# Adafruit_ADG728_1-to-8_Analog_Matrix_Swi.net
KiCad netlist of a schematic drawn in EAGLE
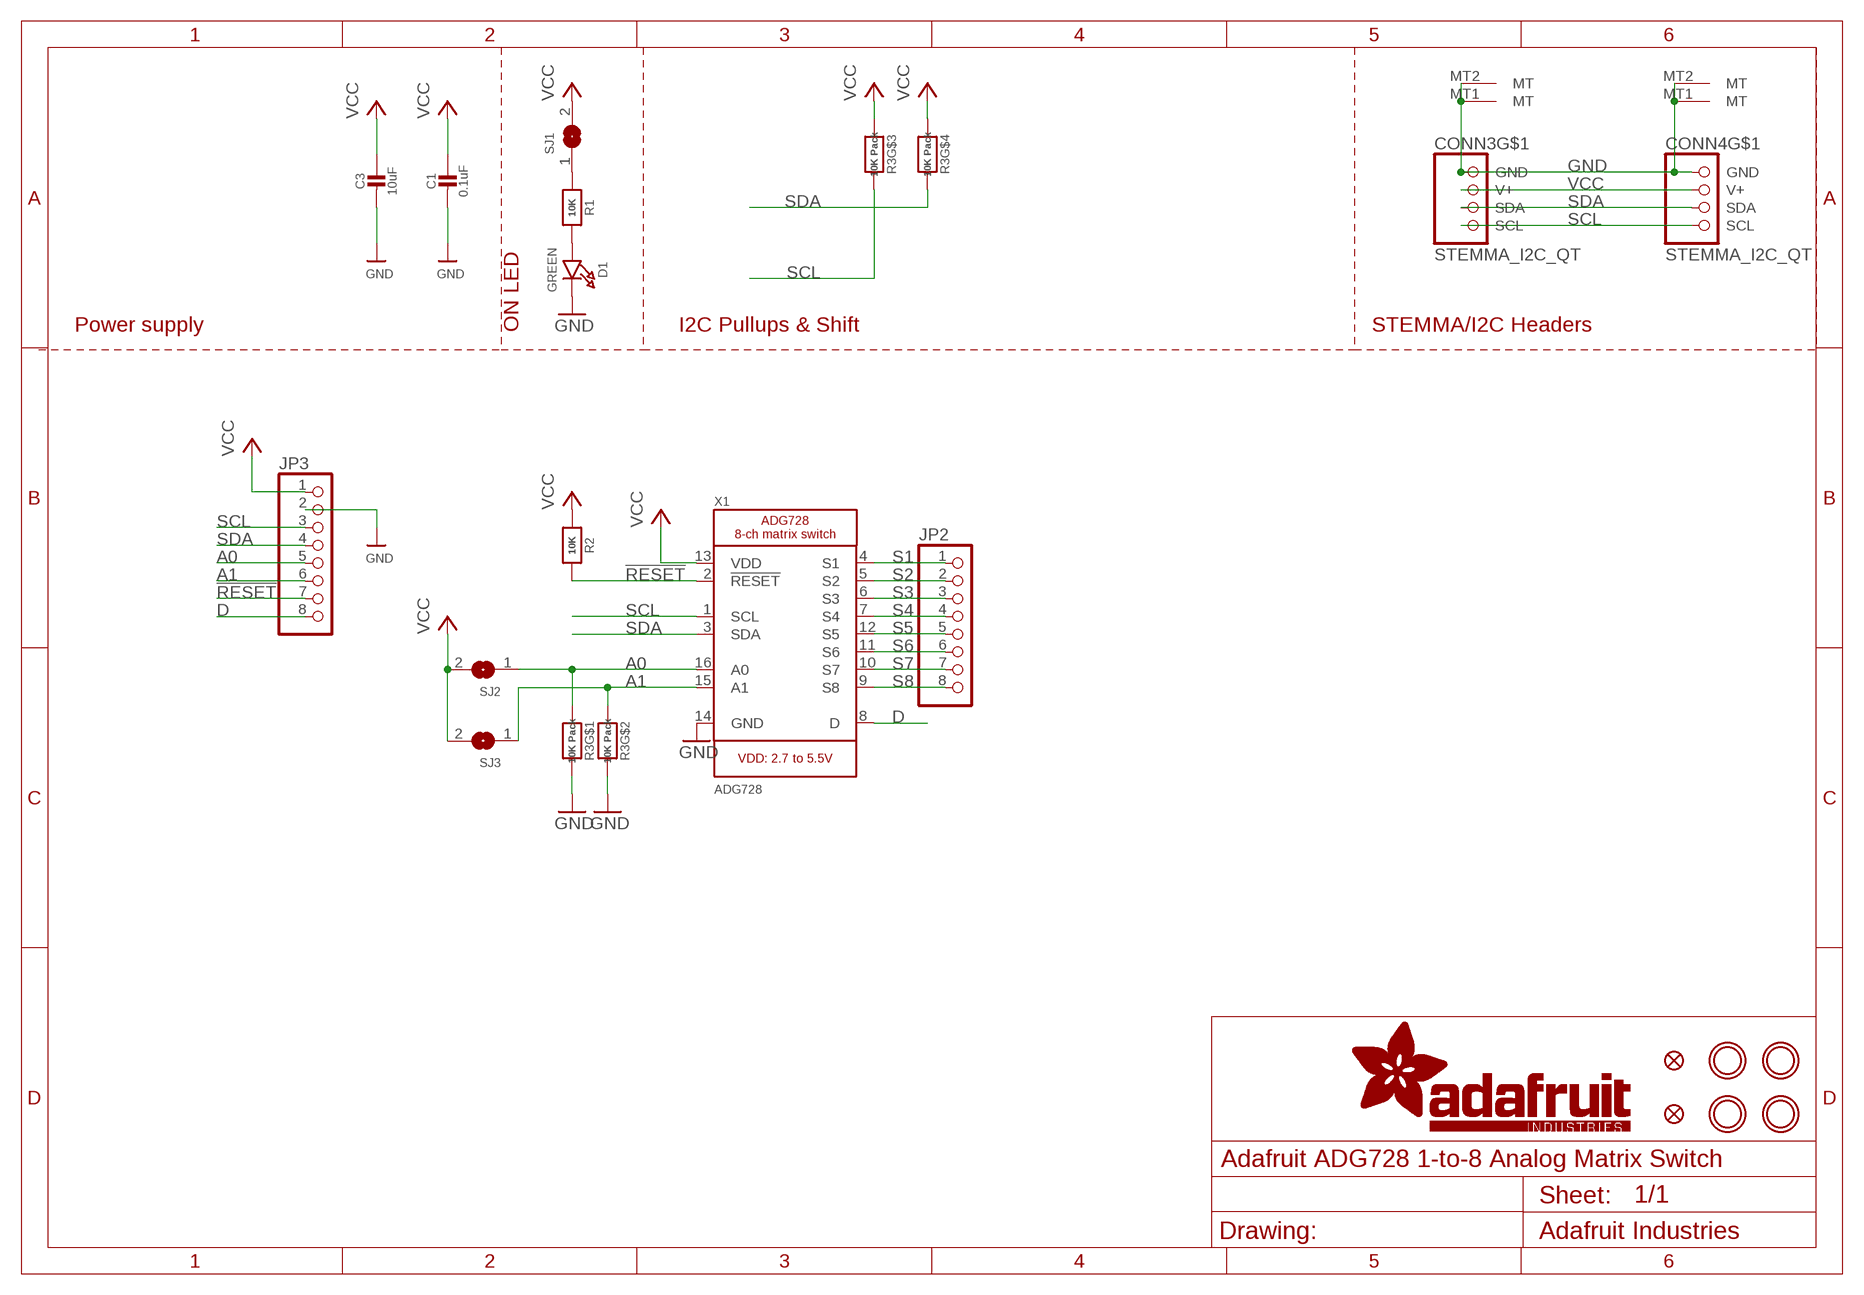
[diagram p0: schematic, sheet 1]

(export (version "E")
  (design (tool "Eeschema 10.0.6"))
  (components
    (comp (ref "C1")
      (value "0.1uF")
      (footprint "eagle-import:0603-NO")
      (libsource (lib "eagle-import") (part "CAP_CERAMIC0603_NO"))
    )
    (comp (ref "C3")
      (value "10uF")
      (footprint "eagle-import:0805-NO")
      (libsource (lib "eagle-import") (part "CAP_CERAMIC0805-NOOUTLINE"))
    )
    (comp (ref "CONN3")
      (value "STEMMA_I2C_QT")
      (footprint "eagle-import:JST_SH4")
      (libsource (lib "eagle-import") (part "STEMMA_I2C_QT"))
    )
    (comp (ref "CONN4")
      (value "STEMMA_I2C_QT")
      (footprint "eagle-import:JST_SH4")
      (libsource (lib "eagle-import") (part "STEMMA_I2C_QT"))
    )
    (comp (ref "D1")
      (value "GREEN")
      (footprint "eagle-import:CHIPLED_0603_NOOUTLINE")
      (libsource (lib "eagle-import") (part "LED0603_NOOUTLINE"))
    )
    (comp (ref "FID3")
      (value "FIDUCIAL_1MM")
      (footprint "eagle-import:FIDUCIAL_1MM")
      (libsource (lib "eagle-import") (part "FIDUCIAL_1MM"))
    )
    (comp (ref "FID4")
      (value "FIDUCIAL_1MM")
      (footprint "eagle-import:FIDUCIAL_1MM")
      (libsource (lib "eagle-import") (part "FIDUCIAL_1MM"))
    )
    (comp (ref "JP2")
      (value "HEADER-1X870MIL")
      (footprint "eagle-import:1X08_ROUND_70")
      (libsource (lib "eagle-import") (part "HEADER-1X870MIL"))
    )
    (comp (ref "JP3")
      (value "HEADER-1X870MIL")
      (footprint "eagle-import:1X08_ROUND_70")
      (libsource (lib "eagle-import") (part "HEADER-1X870MIL"))
    )
    (comp (ref "R1")
      (value "10K")
      (footprint "eagle-import:0603-NO")
      (libsource (lib "eagle-import") (part "RESISTOR_0603_NOOUT"))
    )
    (comp (ref "R2")
      (value "10K")
      (footprint "eagle-import:0603-NO")
      (libsource (lib "eagle-import") (part "RESISTOR_0603_NOOUT"))
    )
    (comp (ref "R3")
      (value "10K Pack")
      (footprint "eagle-import:RESPACK_4X0603")
      (libsource (lib "eagle-import") (part "RESISTOR_4PACK"))
    )
    (comp (ref "SJ1")
      (value "SOLDERJUMPERCLOSED")
      (footprint "eagle-import:SOLDERJUMPER_CLOSEDWIRE")
      (libsource (lib "eagle-import") (part "SOLDERJUMPERCLOSED"))
    )
    (comp (ref "SJ2")
      (value "SOLDERJUMPER")
      (footprint "eagle-import:SOLDERJUMPER_ARROW_NOPASTE")
      (libsource (lib "eagle-import") (part "SOLDERJUMPER"))
    )
    (comp (ref "SJ3")
      (value "SOLDERJUMPER")
      (footprint "eagle-import:SOLDERJUMPER_ARROW_NOPASTE")
      (libsource (lib "eagle-import") (part "SOLDERJUMPER"))
    )
    (comp (ref "U$1")
      (value "MOUNTINGHOLE2.5")
      (footprint "eagle-import:MOUNTINGHOLE_2.5_PLATED")
      (libsource (lib "eagle-import") (part "MOUNTINGHOLE2.5"))
    )
    (comp (ref "U$17")
      (value "MOUNTINGHOLE2.5")
      (footprint "eagle-import:MOUNTINGHOLE_2.5_PLATED")
      (libsource (lib "eagle-import") (part "MOUNTINGHOLE2.5"))
    )
    (comp (ref "U$19")
      (value "MOUNTINGHOLE2.5")
      (footprint "eagle-import:MOUNTINGHOLE_2.5_PLATED")
      (libsource (lib "eagle-import") (part "MOUNTINGHOLE2.5"))
    )
    (comp (ref "U$21")
      (value "MOUNTINGHOLE2.5")
      (footprint "eagle-import:MOUNTINGHOLE_2.5_PLATED")
      (libsource (lib "eagle-import") (part "MOUNTINGHOLE2.5"))
    )
    (comp (ref "X1")
      (value "ADG728")
      (footprint "eagle-import:TSSOP16")
      (libsource (lib "eagle-import") (part "ADG728"))
    )
  )
  (nets
    (net (code "1") (name "/A0") (class "Default")
      (node (ref "JP3") (pin "5") (pinfunction "5_5") (pintype "passive"))
      (node (ref "R3") (pin "1") (pinfunction "1_1") (pintype "passive"))
      (node (ref "SJ2") (pin "1") (pinfunction "1_1") (pintype "passive"))
      (node (ref "X1") (pin "16") (pinfunction "A0_16") (pintype "input"))
    )
    (net (code "2") (name "/A1") (class "Default")
      (node (ref "JP3") (pin "6") (pinfunction "6_6") (pintype "passive"))
      (node (ref "R3") (pin "2") (pinfunction "1_2") (pintype "passive"))
      (node (ref "SJ3") (pin "1") (pinfunction "1_1") (pintype "passive"))
      (node (ref "X1") (pin "15") (pinfunction "A1_15") (pintype "input"))
    )
    (net (code "3") (name "/D") (class "Default")
      (node (ref "JP3") (pin "8") (pinfunction "8_8") (pintype "passive"))
      (node (ref "X1") (pin "8") (pinfunction "D_8") (pintype "input"))
    )
    (net (code "4") (name "/S1") (class "Default")
      (node (ref "JP2") (pin "1") (pinfunction "1_1") (pintype "passive"))
      (node (ref "X1") (pin "4") (pinfunction "S1_4") (pintype "input"))
    )
    (net (code "5") (name "/S2") (class "Default")
      (node (ref "JP2") (pin "2") (pinfunction "2_2") (pintype "passive"))
      (node (ref "X1") (pin "5") (pinfunction "S2_5") (pintype "input"))
    )
    (net (code "6") (name "/S3") (class "Default")
      (node (ref "JP2") (pin "3") (pinfunction "3_3") (pintype "passive"))
      (node (ref "X1") (pin "6") (pinfunction "S3_6") (pintype "input"))
    )
    (net (code "7") (name "/S4") (class "Default")
      (node (ref "JP2") (pin "4") (pinfunction "4_4") (pintype "passive"))
      (node (ref "X1") (pin "7") (pinfunction "S4_7") (pintype "input"))
    )
    (net (code "8") (name "/S5") (class "Default")
      (node (ref "JP2") (pin "5") (pinfunction "5_5") (pintype "passive"))
      (node (ref "X1") (pin "12") (pinfunction "S5_12") (pintype "input"))
    )
    (net (code "9") (name "/S6") (class "Default")
      (node (ref "JP2") (pin "6") (pinfunction "6_6") (pintype "passive"))
      (node (ref "X1") (pin "11") (pinfunction "S6_11") (pintype "input"))
    )
    (net (code "10") (name "/S7") (class "Default")
      (node (ref "JP2") (pin "7") (pinfunction "7_7") (pintype "passive"))
      (node (ref "X1") (pin "10") (pinfunction "S7_10") (pintype "input"))
    )
    (net (code "11") (name "/S8") (class "Default")
      (node (ref "JP2") (pin "8") (pinfunction "8_8") (pintype "passive"))
      (node (ref "X1") (pin "9") (pinfunction "S8_9") (pintype "input"))
    )
    (net (code "12") (name "/SCL") (class "Default")
      (node (ref "CONN3") (pin "4") (pinfunction "SCL_4") (pintype "passive"))
      (node (ref "CONN4") (pin "4") (pinfunction "SCL_4") (pintype "passive"))
      (node (ref "JP3") (pin "3") (pinfunction "3_3") (pintype "passive"))
      (node (ref "R3") (pin "6") (pinfunction "2_6") (pintype "passive"))
      (node (ref "X1") (pin "1") (pinfunction "SCL_1") (pintype "bidirectional"))
    )
    (net (code "13") (name "/SDA") (class "Default")
      (node (ref "CONN3") (pin "3") (pinfunction "SDA_3") (pintype "passive"))
      (node (ref "CONN4") (pin "3") (pinfunction "SDA_3") (pintype "passive"))
      (node (ref "JP3") (pin "4") (pinfunction "4_4") (pintype "passive"))
      (node (ref "R3") (pin "5") (pinfunction "2_5") (pintype "passive"))
      (node (ref "X1") (pin "3") (pinfunction "SDA_3") (pintype "bidirectional"))
    )
    (net (code "14") (name "/~{RESET}") (class "Default")
      (node (ref "JP3") (pin "7") (pinfunction "7_7") (pintype "passive"))
      (node (ref "R2") (pin "2") (pinfunction "2_2") (pintype "passive"))
      (node (ref "X1") (pin "2") (pinfunction "~{RESET}_2") (pintype "input"))
    )
    (net (code "15") (name "GND") (class "Default")
      (node (ref "C1") (pin "2") (pinfunction "2_2") (pintype "passive"))
      (node (ref "C3") (pin "2") (pinfunction "2_2") (pintype "passive"))
      (node (ref "CONN3") (pin "1") (pinfunction "GND_1") (pintype "passive"))
      (node (ref "CONN3") (pin "MT1") (pinfunction "MT_MT1") (pintype "bidirectional"))
      (node (ref "CONN3") (pin "MT2") (pinfunction "MT_MT2") (pintype "bidirectional"))
      (node (ref "CONN4") (pin "1") (pinfunction "GND_1") (pintype "passive"))
      (node (ref "CONN4") (pin "MT1") (pinfunction "MT_MT1") (pintype "bidirectional"))
      (node (ref "CONN4") (pin "MT2") (pinfunction "MT_MT2") (pintype "bidirectional"))
      (node (ref "D1") (pin "C") (pinfunction "C_C") (pintype "passive"))
      (node (ref "JP3") (pin "2") (pinfunction "2_2") (pintype "passive"))
      (node (ref "R3") (pin "7") (pinfunction "2_7") (pintype "passive"))
      (node (ref "R3") (pin "8") (pinfunction "2_8") (pintype "passive"))
      (node (ref "X1") (pin "14") (pinfunction "GND_14") (pintype "power_in"))
    )
    (net (code "16") (name "Net-(D1-PadA)") (class "Default")
      (node (ref "D1") (pin "A") (pinfunction "A_A") (pintype "passive"))
      (node (ref "R1") (pin "2") (pinfunction "2_2") (pintype "passive"))
    )
    (net (code "17") (name "Net-(R1-Pad1)") (class "Default")
      (node (ref "R1") (pin "1") (pinfunction "1_1") (pintype "passive"))
      (node (ref "SJ1") (pin "1") (pinfunction "1_1") (pintype "passive"))
    )
    (net (code "18") (name "VCC") (class "Default")
      (node (ref "C1") (pin "1") (pinfunction "1_1") (pintype "passive"))
      (node (ref "C3") (pin "1") (pinfunction "1_1") (pintype "passive"))
      (node (ref "CONN3") (pin "2") (pinfunction "V+_2") (pintype "passive"))
      (node (ref "CONN4") (pin "2") (pinfunction "V+_2") (pintype "passive"))
      (node (ref "JP3") (pin "1") (pinfunction "1_1") (pintype "passive"))
      (node (ref "R2") (pin "1") (pinfunction "1_1") (pintype "passive"))
      (node (ref "R3") (pin "3") (pinfunction "1_3") (pintype "passive"))
      (node (ref "R3") (pin "4") (pinfunction "1_4") (pintype "passive"))
      (node (ref "SJ1") (pin "2") (pinfunction "2_2") (pintype "passive"))
      (node (ref "SJ2") (pin "2") (pinfunction "2_2") (pintype "passive"))
      (node (ref "SJ3") (pin "2") (pinfunction "2_2") (pintype "passive"))
      (node (ref "X1") (pin "13") (pinfunction "VDD_13") (pintype "power_in"))
    )
  )
)
